# TimeBoard.net
KiCad netlist of a schematic drawn in EAGLE
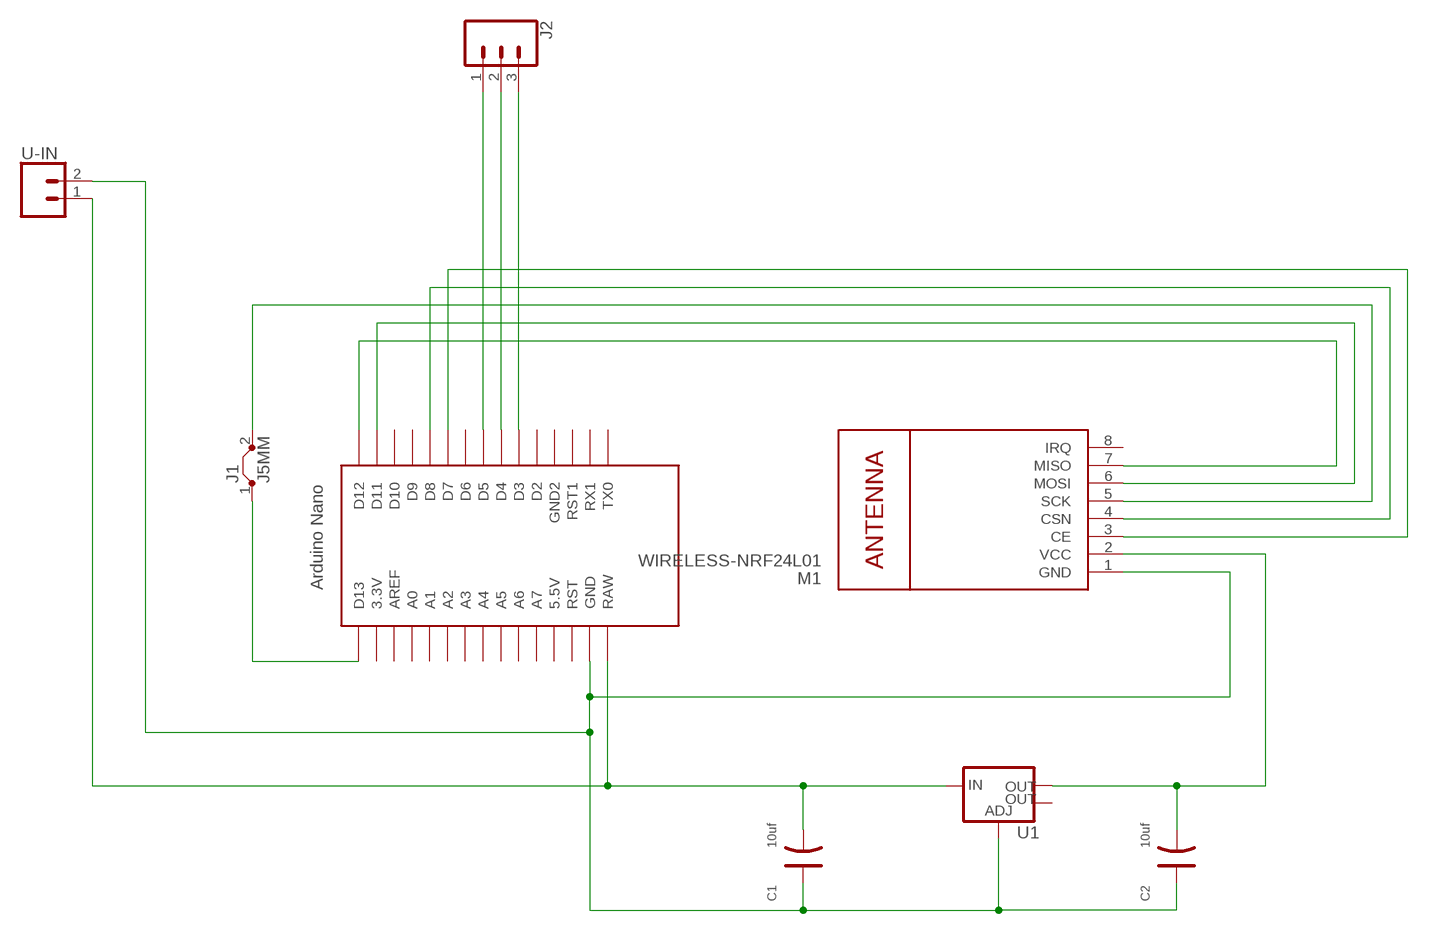
[diagram p0: schematic, sheet 1]

(export (version "E")
  (design (tool "Eeschema 10.0.6"))
  (components
    (comp (ref "C1")
      (value "10uf")
      (footprint "eagle-import:AVX-B")
      (fields (field (name "MPN") "TAJB106K016RNJ"))
      (libsource (lib "eagle-import") (part "TANTALUM-SMD-10UF-16V-10%(AVX-B)"))
    )
    (comp (ref "C2")
      (value "10uf")
      (footprint "eagle-import:AVX-B")
      (fields (field (name "MPN") "TAJB106K016RNJ"))
      (libsource (lib "eagle-import") (part "TANTALUM-SMD-10UF-16V-10%(AVX-B)"))
    )
    (comp (ref "J1")
      (value "J5MM")
      (footprint "eagle-import:05")
      (libsource (lib "eagle-import") (part "J5MM"))
    )
    (comp (ref "J2")
      (value "CONN_03-SCREW-5MM")
      (footprint "eagle-import:SCREWTERMINAL-5MM-3")
      (libsource (lib "eagle-import") (part "CONN_03-SCREW-5MM"))
    )
    (comp (ref "M1")
      (value "WIRELESS-NRF24L01")
      (footprint "eagle-import:WIRELESS-NRF24L01")
      (libsource (lib "eagle-import") (part "WIRELESS-NRF24L01"))
    )
    (comp (ref "U$1")
      (value "NANO")
      (footprint "eagle-import:NANO")
      (libsource (lib "eagle-import") (part "NANO"))
    )
    (comp (ref "U-IN")
      (value "CONN_025MM")
      (footprint "eagle-import:SCREWTERMINAL-5MM-2")
      (libsource (lib "eagle-import") (part "CONN_025MM"))
    )
    (comp (ref "U1")
      (value "V_REG_LM1117SOT223")
      (footprint "eagle-import:SOT223")
      (libsource (lib "eagle-import") (part "V_REG_LM1117SOT223"))
    )
  )
  (nets
    (net (code "1") (name "Net-(J1-Pad1)") (class "Default")
      (node (ref "J1") (pin "1") (pinfunction "1_1") (pintype "passive"))
      (node (ref "U$1") (pin "D13") (pinfunction "D13_D13") (pintype "bidirectional"))
    )
    (net (code "2") (name "Net-(J2-Pad1)") (class "Default")
      (node (ref "J2") (pin "1") (pinfunction "1_1") (pintype "passive"))
      (node (ref "U$1") (pin "D5") (pinfunction "D5_D5") (pintype "bidirectional"))
    )
    (net (code "3") (name "Net-(J2-Pad2)") (class "Default")
      (node (ref "J2") (pin "2") (pinfunction "2_2") (pintype "passive"))
      (node (ref "U$1") (pin "D4") (pinfunction "D4_D4") (pintype "bidirectional"))
    )
    (net (code "4") (name "Net-(J2-Pad3)") (class "Default")
      (node (ref "J2") (pin "3") (pinfunction "3_3") (pintype "passive"))
      (node (ref "U$1") (pin "D3") (pinfunction "D3_D3") (pintype "bidirectional"))
    )
    (net (code "5") (name "Net-(M1-CE)") (class "Default")
      (node (ref "M1") (pin "3") (pinfunction "CE_3") (pintype "bidirectional"))
      (node (ref "U$1") (pin "D7") (pinfunction "D7_D7") (pintype "bidirectional"))
    )
    (net (code "6") (name "Net-(M1-CSN)") (class "Default")
      (node (ref "M1") (pin "4") (pinfunction "CSN_4") (pintype "bidirectional"))
      (node (ref "U$1") (pin "D8") (pinfunction "D8_D8") (pintype "bidirectional"))
    )
    (net (code "7") (name "Net-(M1-GND)") (class "Default")
      (node (ref "C1") (pin "+") (pinfunction "+_+") (pintype "passive"))
      (node (ref "C2") (pin "+") (pinfunction "+_+") (pintype "passive"))
      (node (ref "M1") (pin "1") (pinfunction "GND_1") (pintype "power_in"))
      (node (ref "U$1") (pin "GND") (pinfunction "GND_GND") (pintype "bidirectional"))
      (node (ref "U-IN") (pin "2") (pinfunction "2_2") (pintype "passive"))
      (node (ref "U1") (pin "1") (pinfunction "ADJ_1") (pintype "input"))
    )
    (net (code "8") (name "Net-(M1-MISO)") (class "Default")
      (node (ref "M1") (pin "7") (pinfunction "MISO_7") (pintype "bidirectional"))
      (node (ref "U$1") (pin "D12") (pinfunction "D12_D12") (pintype "bidirectional"))
    )
    (net (code "9") (name "Net-(M1-MOSI)") (class "Default")
      (node (ref "M1") (pin "6") (pinfunction "MOSI_6") (pintype "bidirectional"))
      (node (ref "U$1") (pin "D11") (pinfunction "D11_D11") (pintype "bidirectional"))
    )
    (net (code "10") (name "Net-(M1-SCK)") (class "Default")
      (node (ref "J1") (pin "2") (pinfunction "2_2") (pintype "passive"))
      (node (ref "M1") (pin "5") (pinfunction "SCK_5") (pintype "bidirectional"))
    )
    (net (code "11") (name "Net-(M1-VCC)") (class "Default")
      (node (ref "C2") (pin "-") (pinfunction "-_-") (pintype "passive"))
      (node (ref "M1") (pin "2") (pinfunction "VCC_2") (pintype "power_in"))
      (node (ref "U1") (pin "2") (pinfunction "OUT_2") (pintype "output"))
    )
    (net (code "12") (name "Net-(U1-IN)") (class "Default")
      (node (ref "C1") (pin "-") (pinfunction "-_-") (pintype "passive"))
      (node (ref "U$1") (pin "RAW") (pinfunction "RAW_RAW") (pintype "bidirectional"))
      (node (ref "U-IN") (pin "1") (pinfunction "1_1") (pintype "passive"))
      (node (ref "U1") (pin "3") (pinfunction "IN_3") (pintype "input"))
    )
    (net (code "13") (name "unconnected-(M1-IRQ-Pad8)") (class "Default")
      (node (ref "M1") (pin "8") (pinfunction "IRQ_8") (pintype "bidirectional"))
    )
    (net (code "14") (name "unconnected-(U$1-5.5V-Pad5V)") (class "Default")
      (node (ref "U$1") (pin "5V") (pinfunction "5.5V_5V") (pintype "bidirectional"))
    )
    (net (code "15") (name "unconnected-(U$1-GND2-PadGND1)") (class "Default")
      (node (ref "U$1") (pin "GND1") (pinfunction "GND2_GND1") (pintype "bidirectional"))
    )
    (net (code "16") (name "unconnected-(U$1-Pad3.3V)") (class "Default")
      (node (ref "U$1") (pin "3.3V") (pinfunction "3.3V_3.3V") (pintype "bidirectional"))
    )
    (net (code "17") (name "unconnected-(U$1-PadA0)") (class "Default")
      (node (ref "U$1") (pin "A0") (pinfunction "A0_A0") (pintype "bidirectional"))
    )
    (net (code "18") (name "unconnected-(U$1-PadA1)") (class "Default")
      (node (ref "U$1") (pin "A1") (pinfunction "A1_A1") (pintype "bidirectional"))
    )
    (net (code "19") (name "unconnected-(U$1-PadA2)") (class "Default")
      (node (ref "U$1") (pin "A2") (pinfunction "A2_A2") (pintype "bidirectional"))
    )
    (net (code "20") (name "unconnected-(U$1-PadA3)") (class "Default")
      (node (ref "U$1") (pin "A3") (pinfunction "A3_A3") (pintype "bidirectional"))
    )
    (net (code "21") (name "unconnected-(U$1-PadA4)") (class "Default")
      (node (ref "U$1") (pin "A4") (pinfunction "A4_A4") (pintype "bidirectional"))
    )
    (net (code "22") (name "unconnected-(U$1-PadA5)") (class "Default")
      (node (ref "U$1") (pin "A5") (pinfunction "A5_A5") (pintype "bidirectional"))
    )
    (net (code "23") (name "unconnected-(U$1-PadA6)") (class "Default")
      (node (ref "U$1") (pin "A6") (pinfunction "A6_A6") (pintype "bidirectional"))
    )
    (net (code "24") (name "unconnected-(U$1-PadA7)") (class "Default")
      (node (ref "U$1") (pin "A7") (pinfunction "A7_A7") (pintype "bidirectional"))
    )
    (net (code "25") (name "unconnected-(U$1-PadAREF)") (class "Default")
      (node (ref "U$1") (pin "AREF") (pinfunction "AREF_AREF") (pintype "bidirectional"))
    )
    (net (code "26") (name "unconnected-(U$1-PadD2)") (class "Default")
      (node (ref "U$1") (pin "D2") (pinfunction "D2_D2") (pintype "bidirectional"))
    )
    (net (code "27") (name "unconnected-(U$1-PadD6)") (class "Default")
      (node (ref "U$1") (pin "D6") (pinfunction "D6_D6") (pintype "bidirectional"))
    )
    (net (code "28") (name "unconnected-(U$1-PadD9)") (class "Default")
      (node (ref "U$1") (pin "D9") (pinfunction "D9_D9") (pintype "bidirectional"))
    )
    (net (code "29") (name "unconnected-(U$1-PadD10)") (class "Default")
      (node (ref "U$1") (pin "D10") (pinfunction "D10_D10") (pintype "bidirectional"))
    )
    (net (code "30") (name "unconnected-(U$1-PadICSP1)") (class "Default")
      (node (ref "U$1") (pin "ICSP1") (pinfunction "ICSP1_ICSP1") (pintype "bidirectional"))
    )
    (net (code "31") (name "unconnected-(U$1-PadICSP2)") (class "Default")
      (node (ref "U$1") (pin "ICSP2") (pinfunction "ICSP2_ICSP2") (pintype "bidirectional"))
    )
    (net (code "32") (name "unconnected-(U$1-PadICSP3)") (class "Default")
      (node (ref "U$1") (pin "ICSP3") (pinfunction "ICSP3_ICSP3") (pintype "bidirectional"))
    )
    (net (code "33") (name "unconnected-(U$1-PadICSP4)") (class "Default")
      (node (ref "U$1") (pin "ICSP4") (pinfunction "ICSP4_ICSP4") (pintype "bidirectional"))
    )
    (net (code "34") (name "unconnected-(U$1-PadICSP5)") (class "Default")
      (node (ref "U$1") (pin "ICSP5") (pinfunction "ICSP5_ICSP5") (pintype "bidirectional"))
    )
    (net (code "35") (name "unconnected-(U$1-PadICSP6)") (class "Default")
      (node (ref "U$1") (pin "ICSP6") (pinfunction "ICSP6_ICSP6") (pintype "bidirectional"))
    )
    (net (code "36") (name "unconnected-(U$1-PadRST)") (class "Default")
      (node (ref "U$1") (pin "RST") (pinfunction "RST_RST") (pintype "bidirectional"))
    )
    (net (code "37") (name "unconnected-(U$1-PadRST1)") (class "Default")
      (node (ref "U$1") (pin "RST1") (pinfunction "RST1_RST1") (pintype "bidirectional"))
    )
    (net (code "38") (name "unconnected-(U$1-PadRX1)") (class "Default")
      (node (ref "U$1") (pin "RX1") (pinfunction "RX1_RX1") (pintype "bidirectional"))
    )
    (net (code "39") (name "unconnected-(U$1-PadTX0)") (class "Default")
      (node (ref "U$1") (pin "TX0") (pinfunction "TX0_TX0") (pintype "bidirectional"))
    )
    (net (code "40") (name "unconnected-(U1-OUT-Pad4)") (class "Default")
      (node (ref "U1") (pin "4") (pinfunction "OUT_4") (pintype "output"))
    )
  )
)
